# Peripheral.net
KiCad netlist of a schematic drawn in Altium Designer
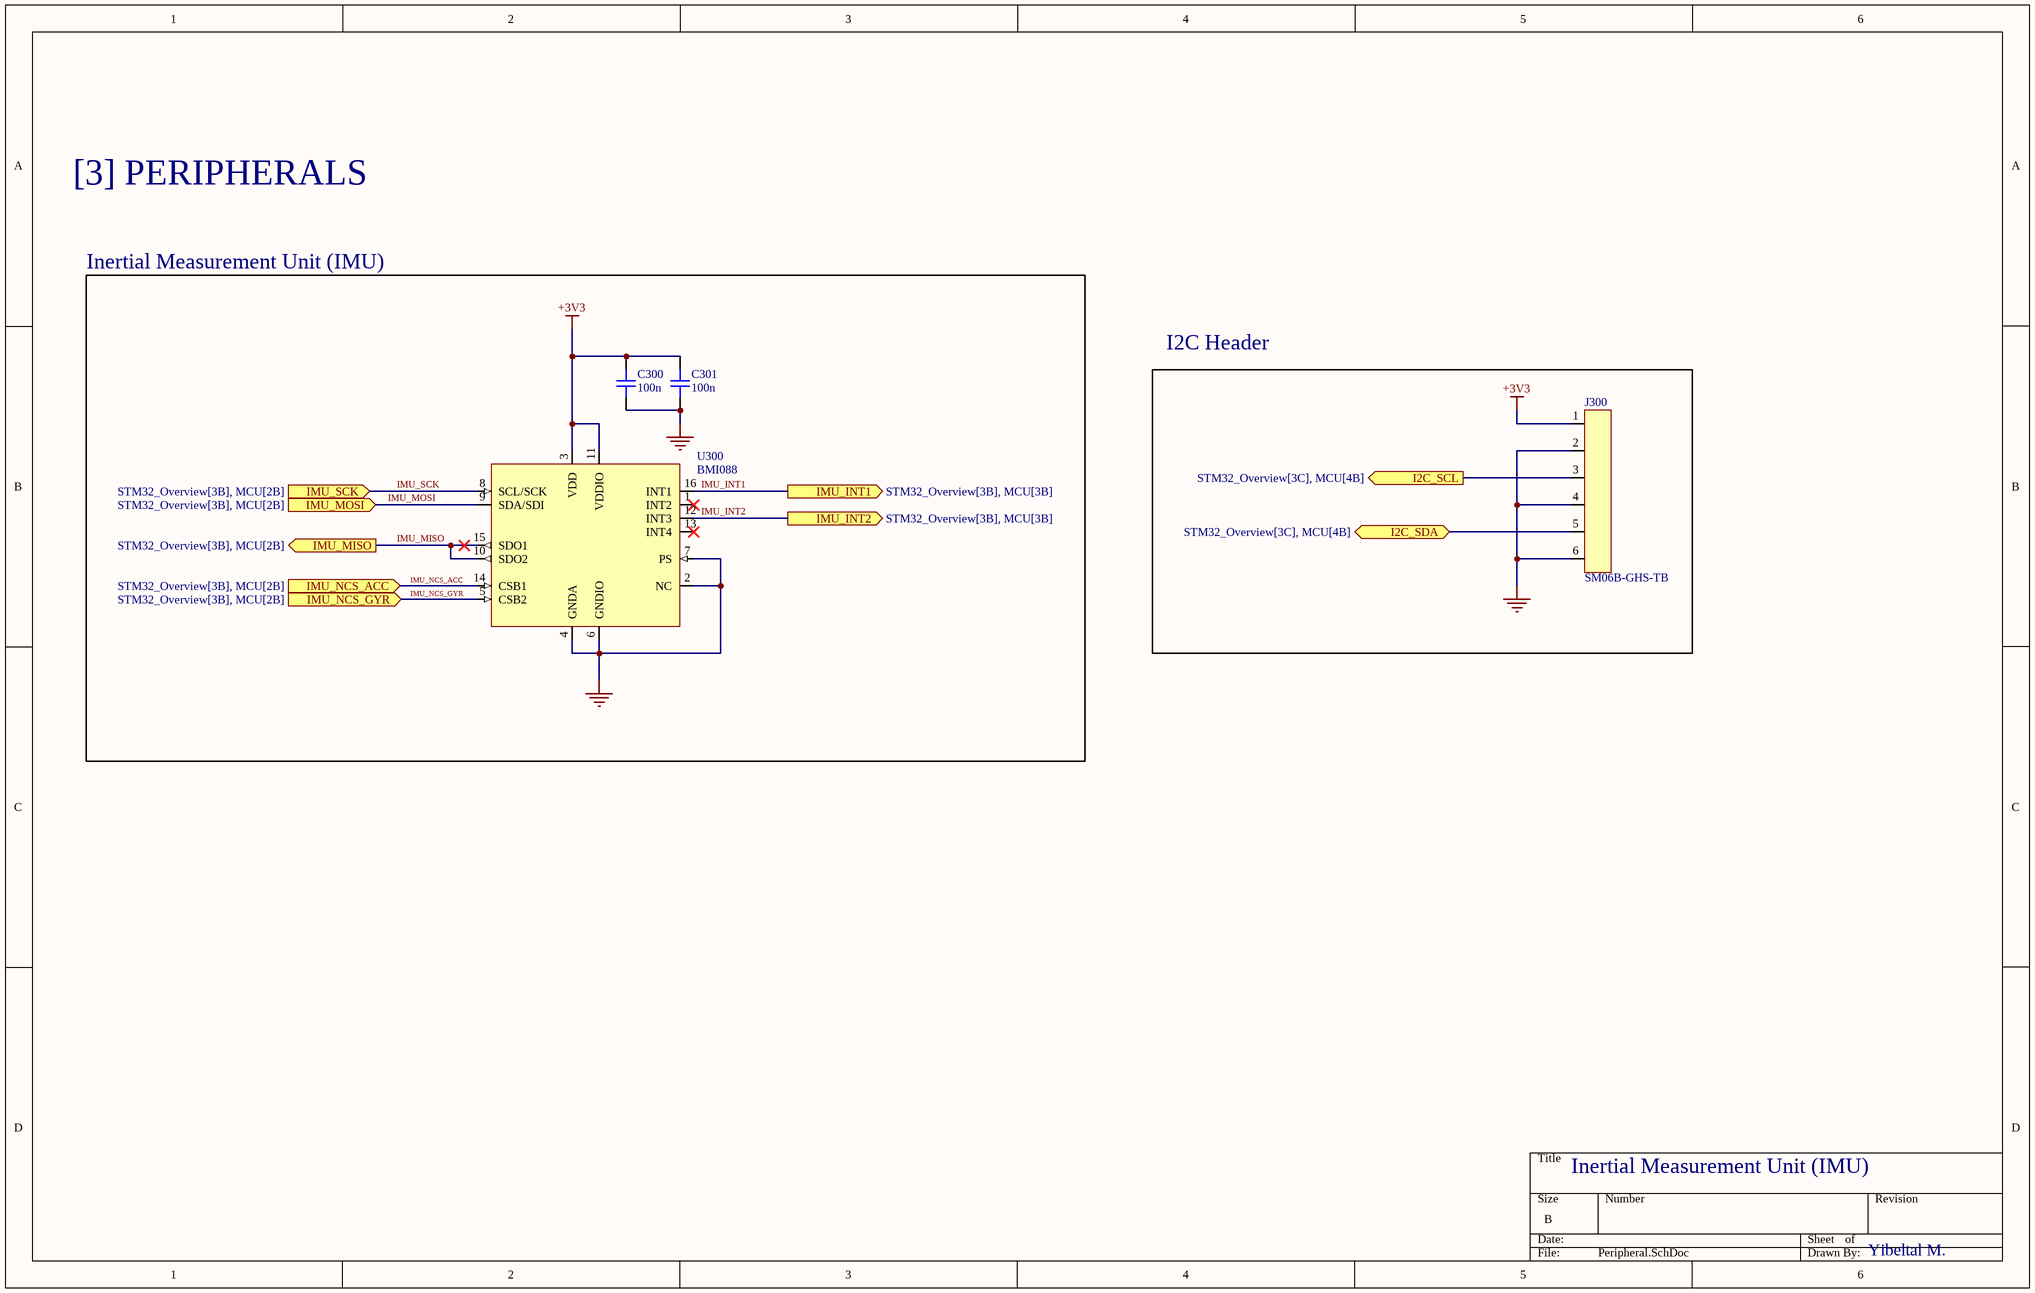
[diagram p0: Peripheral.SchDoc]

(export (version "E")
  (design (tool "Eeschema 10.0.6"))
  (components
    (comp (ref "C300")
      (value "100n")
      (footprint "CAP_0805")
      (description "Capacitor SMD 0805")
      (libsource (lib "Schematic-Lib-PhilsLab (2)") (part "CAP_0805"))
    )
    (comp (ref "C301")
      (value "100n")
      (footprint "CAP_0805")
      (description "Capacitor SMD 0805")
      (libsource (lib "Schematic-Lib-PhilsLab (2)") (part "CAP_0805"))
    )
    (comp (ref "J300")
      (value "SM06B-GHS-TB")
      (footprint "SM06B-GHS-TB")
      (description "Header Connector 6 Position 1.25MM Pitch SMD Horizontal JST GH")
      (fields (field (name "MANUFACTURER") "JST"))
      (libsource (lib "Schematic-Lib-PhilsLab (2)") (part "SM06B-GHS-TB"))
    )
    (comp (ref "U300")
      (value "BMI088")
      (footprint "BMI088")
      (description "Inertial Measurement Unit IMU 6-Axis LGA")
      (fields (field (name "MANUFACTURER") "Bosch"))
      (libsource (lib "Schematic-Lib-PhilsLab (2)") (part "BMI088"))
    )
  )
  (nets
    (net (code "1") (name "+3V3") (class "Default")
      (node (ref "C300") (pin "2") (pinfunction "2_2") (pintype "passive"))
      (node (ref "C301") (pin "2") (pinfunction "2_2") (pintype "passive"))
      (node (ref "J300") (pin "1") (pinfunction "1_1") (pintype "passive"))
      (node (ref "U300") (pin "11") (pinfunction "VDDIO_11") (pintype "power_in"))
      (node (ref "U300") (pin "3") (pinfunction "VDD_3") (pintype "power_in"))
    )
    (net (code "2") (name "/I2C_SCL") (class "Default")
      (node (ref "J300") (pin "3") (pinfunction "3_3") (pintype "passive"))
    )
    (net (code "3") (name "/I2C_SDA") (class "Default")
      (node (ref "J300") (pin "5") (pinfunction "5_5") (pintype "passive"))
    )
    (net (code "4") (name "/IMU_INT1") (class "Default")
      (node (ref "U300") (pin "16") (pinfunction "INT1_16") (pintype "bidirectional"))
    )
    (net (code "5") (name "/IMU_INT2") (class "Default")
      (node (ref "U300") (pin "12") (pinfunction "INT3_12") (pintype "bidirectional"))
    )
    (net (code "6") (name "/IMU_MISO") (class "Default")
      (node (ref "U300") (pin "10") (pinfunction "SDO2_10") (pintype "output"))
      (node (ref "U300") (pin "15") (pinfunction "SDO1_15") (pintype "output"))
    )
    (net (code "7") (name "/IMU_MOSI") (class "Default")
      (node (ref "U300") (pin "9") (pinfunction "SDA/SDI_9") (pintype "bidirectional"))
    )
    (net (code "8") (name "/IMU_NCS_ACC") (class "Default")
      (node (ref "U300") (pin "14") (pinfunction "CSB1_14") (pintype "input"))
    )
    (net (code "9") (name "/IMU_NCS_GYR") (class "Default")
      (node (ref "U300") (pin "5") (pinfunction "CSB2_5") (pintype "input"))
    )
    (net (code "10") (name "/IMU_SCK") (class "Default")
      (node (ref "U300") (pin "8") (pinfunction "SCL/SCK_8") (pintype "input"))
    )
    (net (code "11") (name "GND") (class "Default")
      (node (ref "C300") (pin "1") (pinfunction "1_1") (pintype "passive"))
      (node (ref "C301") (pin "1") (pinfunction "1_1") (pintype "passive"))
      (node (ref "J300") (pin "2") (pinfunction "2_2") (pintype "passive"))
      (node (ref "J300") (pin "4") (pinfunction "4_4") (pintype "passive"))
      (node (ref "J300") (pin "6") (pinfunction "6_6") (pintype "passive"))
      (node (ref "U300") (pin "2") (pinfunction "NC_2") (pintype "passive"))
      (node (ref "U300") (pin "4") (pinfunction "GNDA_4") (pintype "power_in"))
      (node (ref "U300") (pin "6") (pinfunction "GNDIO_6") (pintype "power_in"))
      (node (ref "U300") (pin "7") (pinfunction "PS_7") (pintype "input"))
    )
    (net (code "12") (name "unconnected-(U300-INT2-Pad1)") (class "Default")
      (node (ref "U300") (pin "1") (pinfunction "INT2_1") (pintype "bidirectional+no_connect"))
    )
    (net (code "13") (name "unconnected-(U300-INT4-Pad13)") (class "Default")
      (node (ref "U300") (pin "13") (pinfunction "INT4_13") (pintype "bidirectional+no_connect"))
    )
  )
)
